# modEEGamp_v1_1.net
KiCad netlist of a schematic drawn in EAGLE
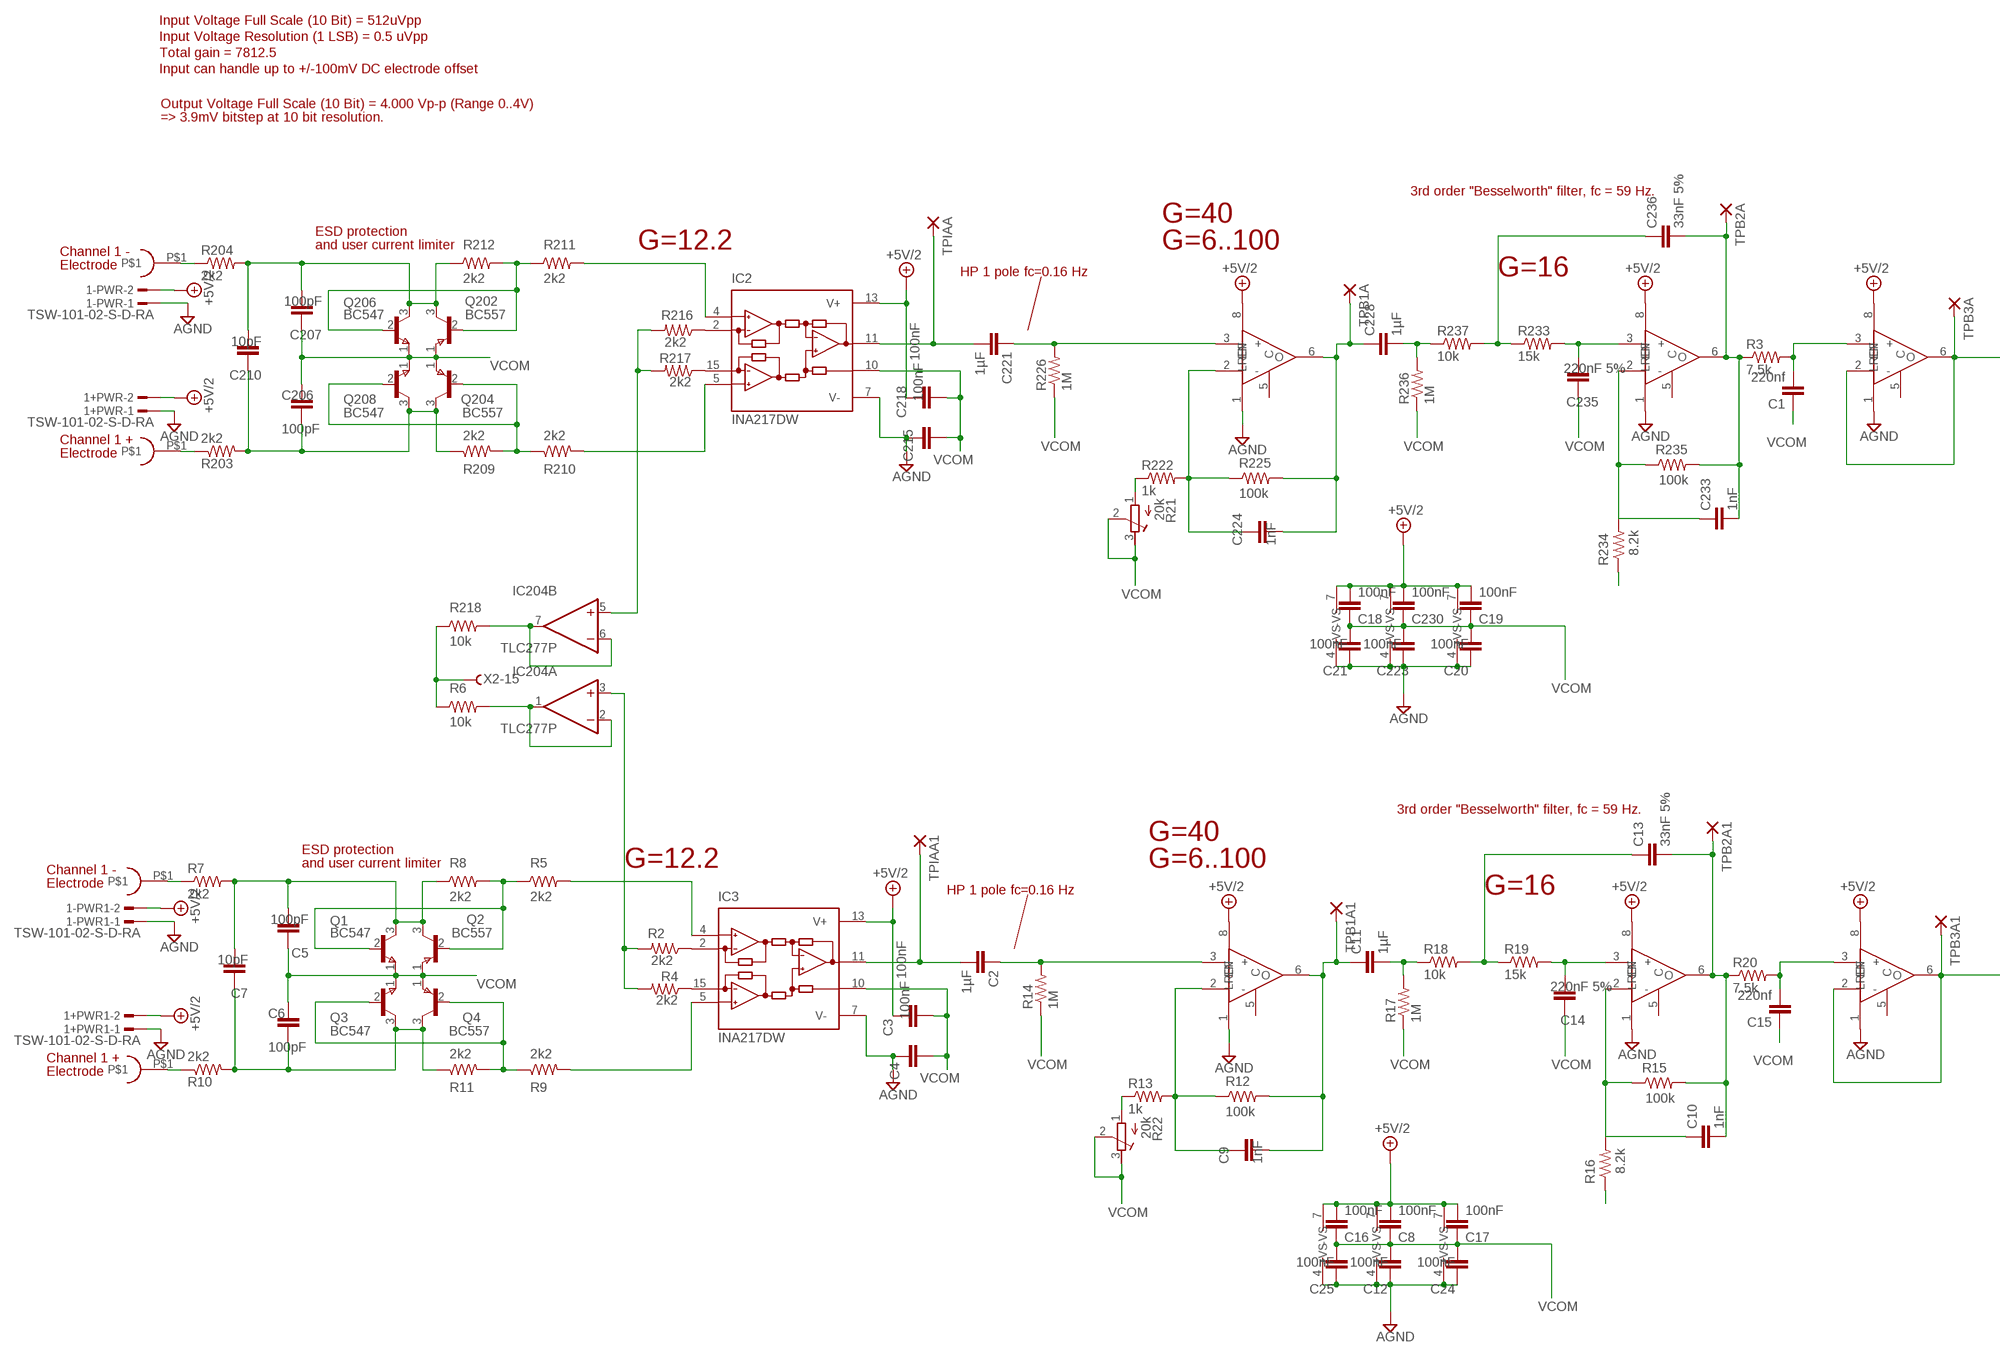
[diagram p0: schematic, sheet 1, part 1 of 2]
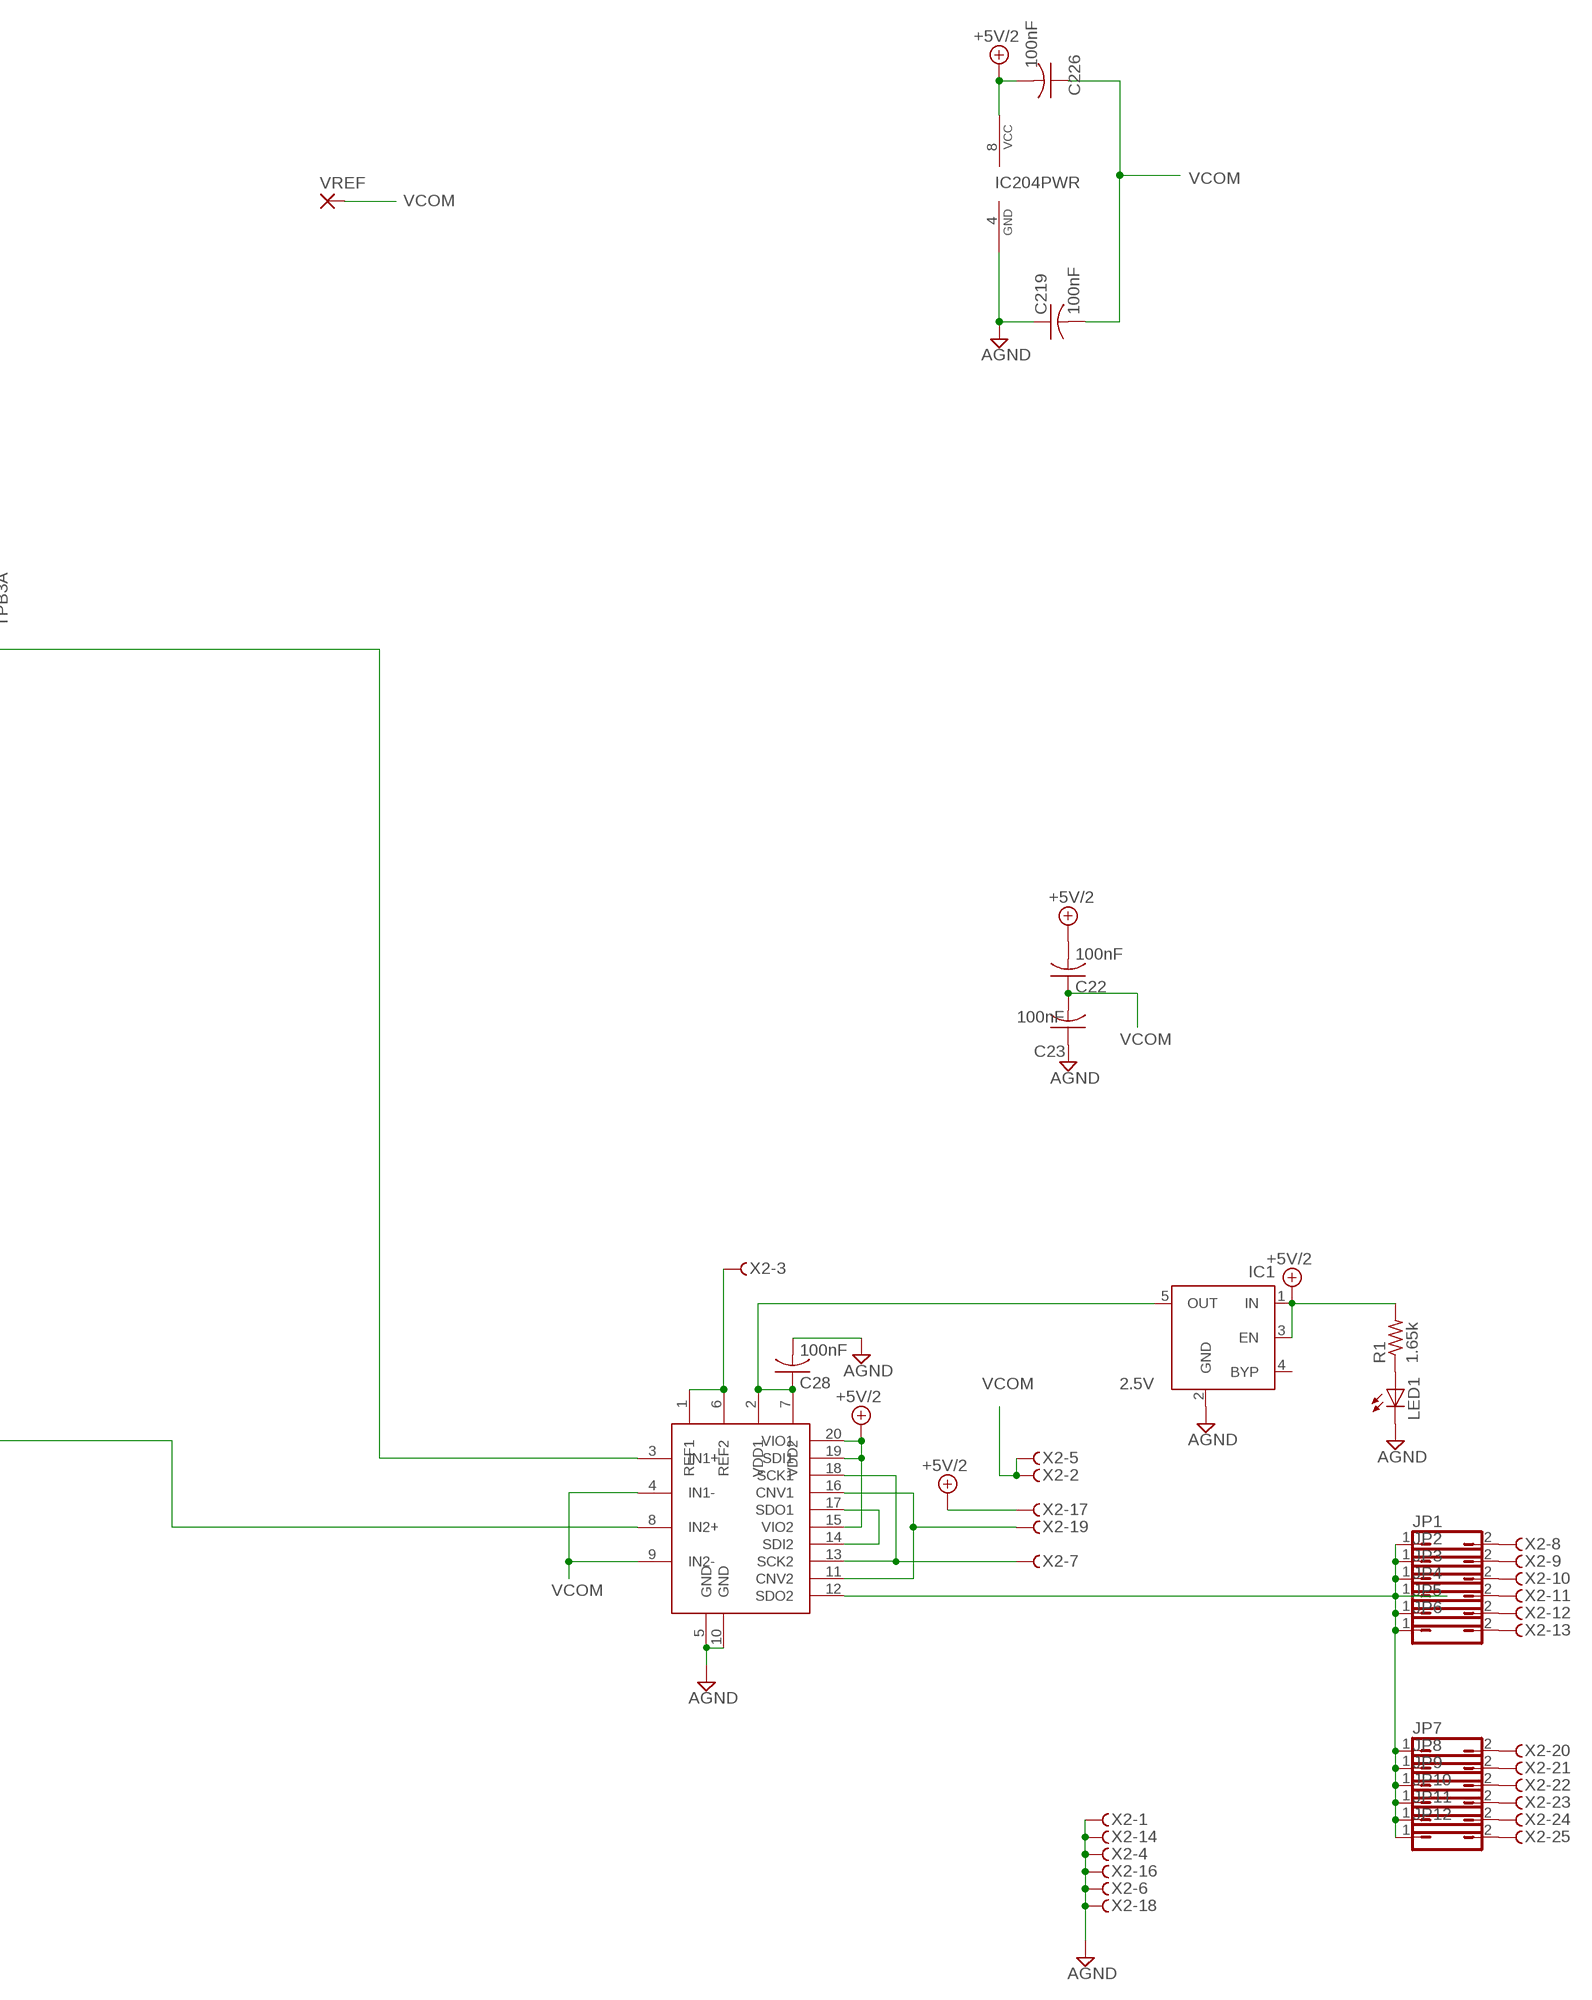
[diagram p1: schematic, sheet 1, part 2 of 2]

(export (version "E")
  (design (tool "Eeschema 10.0.6"))
  (components
    (comp (ref "1+PWR")
      (value "TSW-101-02-S-D-RA")
      (footprint "eagle-import:TSW-101-02-S-D-RA")
      (libsource (lib "eagle-import") (part "TSW-101-02-S-D-RA"))
    )
    (comp (ref "1+PWR1")
      (value "TSW-101-02-S-D-RA")
      (footprint "eagle-import:TSW-101-02-S-D-RA")
      (libsource (lib "eagle-import") (part "TSW-101-02-S-D-RA"))
    )
    (comp (ref "1-PWR")
      (value "TSW-101-02-S-D-RA")
      (footprint "eagle-import:TSW-101-02-S-D-RA")
      (libsource (lib "eagle-import") (part "TSW-101-02-S-D-RA"))
    )
    (comp (ref "1-PWR1")
      (value "TSW-101-02-S-D-RA")
      (footprint "eagle-import:TSW-101-02-S-D-RA")
      (libsource (lib "eagle-import") (part "TSW-101-02-S-D-RA"))
    )
    (comp (ref "C1")
      (value "220nf")
      (footprint "eagle-import:C1206")
      (libsource (lib "eagle-import") (part "C-EUC1206"))
    )
    (comp (ref "C1+")
      (value "DIN42802")
      (footprint "eagle-import:DIN42802")
      (libsource (lib "eagle-import") (part "DIN42802"))
    )
    (comp (ref "C1+1")
      (value "DIN42802")
      (footprint "eagle-import:DIN42802")
      (libsource (lib "eagle-import") (part "DIN42802"))
    )
    (comp (ref "C1-")
      (value "DIN42802")
      (footprint "eagle-import:DIN42802")
      (libsource (lib "eagle-import") (part "DIN42802"))
    )
    (comp (ref "C1-1")
      (value "DIN42802")
      (footprint "eagle-import:DIN42802")
      (libsource (lib "eagle-import") (part "DIN42802"))
    )
    (comp (ref "C2")
      (value "1µF")
      (footprint "eagle-import:C050-024X044")
      (libsource (lib "eagle-import") (part "C-EU050-024X044"))
    )
    (comp (ref "C3")
      (value "100nF")
      (footprint "eagle-import:C1206")
      (libsource (lib "eagle-import") (part "C-EUC1206"))
    )
    (comp (ref "C4")
      (value "100nF")
      (footprint "eagle-import:C1206")
      (libsource (lib "eagle-import") (part "C-EUC1206"))
    )
    (comp (ref "C5")
      (value "100pF")
      (footprint "eagle-import:C1206")
      (libsource (lib "eagle-import") (part "C-EUC1206"))
    )
    (comp (ref "C6")
      (value "100pF")
      (footprint "eagle-import:C1206")
      (libsource (lib "eagle-import") (part "C-EUC1206"))
    )
    (comp (ref "C7")
      (value "10pF")
      (footprint "eagle-import:C1206")
      (libsource (lib "eagle-import") (part "C-EUC1206"))
    )
    (comp (ref "C8")
      (value "100nF")
      (footprint "eagle-import:C1206")
      (libsource (lib "eagle-import") (part "C-EUC1206"))
    )
    (comp (ref "C9")
      (value "1nF")
      (footprint "eagle-import:C1206")
      (libsource (lib "eagle-import") (part "C-EUC1206"))
    )
    (comp (ref "C10")
      (value "1nF")
      (footprint "eagle-import:C1206")
      (libsource (lib "eagle-import") (part "C-EUC1206"))
    )
    (comp (ref "C11")
      (value "1µF")
      (footprint "eagle-import:C050-024X044")
      (libsource (lib "eagle-import") (part "C-EU050-024X044"))
    )
    (comp (ref "C12")
      (value "100nF")
      (footprint "eagle-import:C1206")
      (libsource (lib "eagle-import") (part "C-EUC1206"))
    )
    (comp (ref "C13")
      (value "33nF 5%")
      (footprint "eagle-import:C1206")
      (libsource (lib "eagle-import") (part "C-EUC1206"))
    )
    (comp (ref "C14")
      (value "220nF 5%")
      (footprint "eagle-import:C1206")
      (libsource (lib "eagle-import") (part "C-EUC1206"))
    )
    (comp (ref "C15")
      (value "220nf")
      (footprint "eagle-import:C1206")
      (libsource (lib "eagle-import") (part "C-EUC1206"))
    )
    (comp (ref "C16")
      (value "100nF")
      (footprint "eagle-import:C1206")
      (libsource (lib "eagle-import") (part "C-EUC1206"))
    )
    (comp (ref "C17")
      (value "100nF")
      (footprint "eagle-import:C1206")
      (libsource (lib "eagle-import") (part "C-EUC1206"))
    )
    (comp (ref "C18")
      (value "100nF")
      (footprint "eagle-import:C1206")
      (libsource (lib "eagle-import") (part "C-EUC1206"))
    )
    (comp (ref "C19")
      (value "100nF")
      (footprint "eagle-import:C1206")
      (libsource (lib "eagle-import") (part "C-EUC1206"))
    )
    (comp (ref "C20")
      (value "100nF")
      (footprint "eagle-import:C1206")
      (libsource (lib "eagle-import") (part "C-EUC1206"))
    )
    (comp (ref "C21")
      (value "100nF")
      (footprint "eagle-import:C1206")
      (libsource (lib "eagle-import") (part "C-EUC1206"))
    )
    (comp (ref "C22")
      (value "100nF")
      (footprint "eagle-import:C1206")
      (libsource (lib "eagle-import") (part "C-USC1206"))
    )
    (comp (ref "C23")
      (value "100nF")
      (footprint "eagle-import:C1206")
      (libsource (lib "eagle-import") (part "C-USC1206"))
    )
    (comp (ref "C24")
      (value "100nF")
      (footprint "eagle-import:C1206")
      (libsource (lib "eagle-import") (part "C-EUC1206"))
    )
    (comp (ref "C25")
      (value "100nF")
      (footprint "eagle-import:C1206")
      (libsource (lib "eagle-import") (part "C-EUC1206"))
    )
    (comp (ref "C28")
      (value "100nF")
      (footprint "eagle-import:C1206")
      (libsource (lib "eagle-import") (part "C-USC1206"))
    )
    (comp (ref "C206")
      (value "100pF")
      (footprint "eagle-import:C1206")
      (libsource (lib "eagle-import") (part "C-EUC1206"))
    )
    (comp (ref "C207")
      (value "100pF")
      (footprint "eagle-import:C1206")
      (libsource (lib "eagle-import") (part "C-EUC1206"))
    )
    (comp (ref "C210")
      (value "10pF")
      (footprint "eagle-import:C1206")
      (libsource (lib "eagle-import") (part "C-EUC1206"))
    )
    (comp (ref "C215")
      (value "100nF")
      (footprint "eagle-import:C1206")
      (libsource (lib "eagle-import") (part "C-EUC1206"))
    )
    (comp (ref "C218")
      (value "100nF")
      (footprint "eagle-import:C1206")
      (libsource (lib "eagle-import") (part "C-EUC1206"))
    )
    (comp (ref "C219")
      (value "100nF")
      (footprint "eagle-import:C1206")
      (libsource (lib "eagle-import") (part "C-USC1206"))
    )
    (comp (ref "C221")
      (value "1µF")
      (footprint "eagle-import:C050-024X044")
      (libsource (lib "eagle-import") (part "C-EU050-024X044"))
    )
    (comp (ref "C223")
      (value "100nF")
      (footprint "eagle-import:C1206")
      (libsource (lib "eagle-import") (part "C-EUC1206"))
    )
    (comp (ref "C224")
      (value "1nF")
      (footprint "eagle-import:C1206")
      (libsource (lib "eagle-import") (part "C-EUC1206"))
    )
    (comp (ref "C226")
      (value "100nF")
      (footprint "eagle-import:C1206")
      (libsource (lib "eagle-import") (part "C-USC1206"))
    )
    (comp (ref "C228")
      (value "1µF")
      (footprint "eagle-import:C050-024X044")
      (libsource (lib "eagle-import") (part "C-EU050-024X044"))
    )
    (comp (ref "C230")
      (value "100nF")
      (footprint "eagle-import:C1206")
      (libsource (lib "eagle-import") (part "C-EUC1206"))
    )
    (comp (ref "C233")
      (value "1nF")
      (footprint "eagle-import:C1206")
      (libsource (lib "eagle-import") (part "C-EUC1206"))
    )
    (comp (ref "C235")
      (value "220nF 5%")
      (footprint "eagle-import:C1206")
      (libsource (lib "eagle-import") (part "C-EUC1206"))
    )
    (comp (ref "C236")
      (value "33nF 5%")
      (footprint "eagle-import:C1206")
      (libsource (lib "eagle-import") (part "C-EUC1206"))
    )
    (comp (ref "IC1")
      (value "2.5V")
      (footprint "eagle-import:SOT23-5")
      (libsource (lib "eagle-import") (part "MIC5219XX"))
    )
    (comp (ref "IC2")
      (value "INA217DW")
      (footprint "eagle-import:DW_RPDSO-G16")
      (fields (field (name "MF") "TEXAS INSTRUMENTS") (field (name "MPN") "INA217AIDWT"))
      (libsource (lib "eagle-import") (part "INA217DW"))
    )
    (comp (ref "IC3")
      (value "INA217DW")
      (footprint "eagle-import:DW_RPDSO-G16")
      (fields (field (name "MF") "TEXAS INSTRUMENTS") (field (name "MPN") "INA217AIDWT"))
      (libsource (lib "eagle-import") (part "INA217DW"))
    )
    (comp (ref "IC204")
      (value "TLC277P")
      (footprint "eagle-import:DIL-08")
      (libsource (lib "eagle-import") (part "TLC277P"))
    )
    (comp (ref "JP1")
      (value "JP1Q")
      (footprint "eagle-import:JP1")
      (libsource (lib "eagle-import") (part "JP1Q"))
    )
    (comp (ref "JP2")
      (value "JP1Q")
      (footprint "eagle-import:JP1")
      (libsource (lib "eagle-import") (part "JP1Q"))
    )
    (comp (ref "JP3")
      (value "JP1Q")
      (footprint "eagle-import:JP1")
      (libsource (lib "eagle-import") (part "JP1Q"))
    )
    (comp (ref "JP4")
      (value "JP1Q")
      (footprint "eagle-import:JP1")
      (libsource (lib "eagle-import") (part "JP1Q"))
    )
    (comp (ref "JP5")
      (value "JP1Q")
      (footprint "eagle-import:JP1")
      (libsource (lib "eagle-import") (part "JP1Q"))
    )
    (comp (ref "JP6")
      (value "JP1Q")
      (footprint "eagle-import:JP1")
      (libsource (lib "eagle-import") (part "JP1Q"))
    )
    (comp (ref "JP7")
      (value "JP1Q")
      (footprint "eagle-import:JP1")
      (libsource (lib "eagle-import") (part "JP1Q"))
    )
    (comp (ref "JP8")
      (value "JP1Q")
      (footprint "eagle-import:JP1")
      (libsource (lib "eagle-import") (part "JP1Q"))
    )
    (comp (ref "JP9")
      (value "JP1Q")
      (footprint "eagle-import:JP1")
      (libsource (lib "eagle-import") (part "JP1Q"))
    )
    (comp (ref "JP10")
      (value "JP1Q")
      (footprint "eagle-import:JP1")
      (libsource (lib "eagle-import") (part "JP1Q"))
    )
    (comp (ref "JP11")
      (value "JP1Q")
      (footprint "eagle-import:JP1")
      (libsource (lib "eagle-import") (part "JP1Q"))
    )
    (comp (ref "JP12")
      (value "JP1Q")
      (footprint "eagle-import:JP1")
      (libsource (lib "eagle-import") (part "JP1Q"))
    )
    (comp (ref "LED1")
      (value "LED3MM")
      (footprint "eagle-import:LED3MM")
      (libsource (lib "eagle-import") (part "LED3MM"))
    )
    (comp (ref "Q1")
      (value "BC547")
      (footprint "eagle-import:TO92")
      (libsource (lib "eagle-import") (part "BC547"))
    )
    (comp (ref "Q2")
      (value "BC557")
      (footprint "eagle-import:TO92")
      (libsource (lib "eagle-import") (part "BC557"))
    )
    (comp (ref "Q3")
      (value "BC547")
      (footprint "eagle-import:TO92")
      (libsource (lib "eagle-import") (part "BC547"))
    )
    (comp (ref "Q4")
      (value "BC557")
      (footprint "eagle-import:TO92")
      (libsource (lib "eagle-import") (part "BC557"))
    )
    (comp (ref "Q202")
      (value "BC557")
      (footprint "eagle-import:TO92")
      (libsource (lib "eagle-import") (part "BC557"))
    )
    (comp (ref "Q204")
      (value "BC557")
      (footprint "eagle-import:TO92")
      (libsource (lib "eagle-import") (part "BC557"))
    )
    (comp (ref "Q206")
      (value "BC547")
      (footprint "eagle-import:TO92")
      (libsource (lib "eagle-import") (part "BC547"))
    )
    (comp (ref "Q208")
      (value "BC547")
      (footprint "eagle-import:TO92")
      (libsource (lib "eagle-import") (part "BC547"))
    )
    (comp (ref "R1")
      (value "1.65k")
      (footprint "eagle-import:R1206")
      (libsource (lib "eagle-import") (part "R-US_R1206"))
    )
    (comp (ref "R2")
      (value "2k2")
      (footprint "eagle-import:R1206")
      (libsource (lib "eagle-import") (part "R-US_R1206"))
    )
    (comp (ref "R3")
      (value "7.5k")
      (footprint "eagle-import:R1206")
      (libsource (lib "eagle-import") (part "R-US_R1206"))
    )
    (comp (ref "R4")
      (value "2k2")
      (footprint "eagle-import:R1206")
      (libsource (lib "eagle-import") (part "R-US_R1206"))
    )
    (comp (ref "R5")
      (value "2k2")
      (footprint "eagle-import:R1206")
      (libsource (lib "eagle-import") (part "R-US_R1206"))
    )
    (comp (ref "R6")
      (value "10k")
      (footprint "eagle-import:R1206")
      (libsource (lib "eagle-import") (part "R-US_R1206"))
    )
    (comp (ref "R7")
      (value "2k2")
      (footprint "eagle-import:R1206")
      (libsource (lib "eagle-import") (part "R-US_R1206"))
    )
    (comp (ref "R8")
      (value "2k2")
      (footprint "eagle-import:R1206")
      (libsource (lib "eagle-import") (part "R-US_R1206"))
    )
    (comp (ref "R9")
      (value "2k2")
      (footprint "eagle-import:R1206")
      (libsource (lib "eagle-import") (part "R-US_R1206"))
    )
    (comp (ref "R10")
      (value "2k2")
      (footprint "eagle-import:R1206")
      (libsource (lib "eagle-import") (part "R-US_R1206"))
    )
    (comp (ref "R11")
      (value "2k2")
      (footprint "eagle-import:R1206")
      (libsource (lib "eagle-import") (part "R-US_R1206"))
    )
    (comp (ref "R12")
      (value "100k")
      (footprint "eagle-import:R1206")
      (libsource (lib "eagle-import") (part "R-US_R1206"))
    )
    (comp (ref "R13")
      (value "1k")
      (footprint "eagle-import:R1206")
      (libsource (lib "eagle-import") (part "R-US_R1206"))
    )
    (comp (ref "R14")
      (value "1M")
      (footprint "eagle-import:R1206")
      (libsource (lib "eagle-import") (part "R-US_R1206"))
    )
    (comp (ref "R15")
      (value "100k")
      (footprint "eagle-import:R1206")
      (libsource (lib "eagle-import") (part "R-US_R1206"))
    )
    (comp (ref "R16")
      (value "8.2k")
      (footprint "eagle-import:R1206")
      (libsource (lib "eagle-import") (part "R-US_R1206"))
    )
    (comp (ref "R17")
      (value "1M")
      (footprint "eagle-import:R1206")
      (libsource (lib "eagle-import") (part "R-US_R1206"))
    )
    (comp (ref "R18")
      (value "10k")
      (footprint "eagle-import:R1206")
      (libsource (lib "eagle-import") (part "R-US_R1206"))
    )
    (comp (ref "R19")
      (value "15k")
      (footprint "eagle-import:R1206")
      (libsource (lib "eagle-import") (part "R-US_R1206"))
    )
    (comp (ref "R20")
      (value "7.5k")
      (footprint "eagle-import:R1206")
      (libsource (lib "eagle-import") (part "R-US_R1206"))
    )
    (comp (ref "R21")
      (value "20k")
      (footprint "eagle-import:RTRIM3296W")
      (libsource (lib "eagle-import") (part "R-TRIMM3296W"))
    )
    (comp (ref "R22")
      (value "20k")
      (footprint "eagle-import:RTRIM3296W")
      (libsource (lib "eagle-import") (part "R-TRIMM3296W"))
    )
    (comp (ref "R203")
      (value "2k2")
      (footprint "eagle-import:R1206")
      (libsource (lib "eagle-import") (part "R-US_R1206"))
    )
    (comp (ref "R204")
      (value "2k2")
      (footprint "eagle-import:R1206")
      (libsource (lib "eagle-import") (part "R-US_R1206"))
    )
    (comp (ref "R209")
      (value "2k2")
      (footprint "eagle-import:R1206")
      (libsource (lib "eagle-import") (part "R-US_R1206"))
    )
    (comp (ref "R210")
      (value "2k2")
      (footprint "eagle-import:R1206")
      (libsource (lib "eagle-import") (part "R-US_R1206"))
    )
    (comp (ref "R211")
      (value "2k2")
      (footprint "eagle-import:R1206")
      (libsource (lib "eagle-import") (part "R-US_R1206"))
    )
    (comp (ref "R212")
      (value "2k2")
      (footprint "eagle-import:R1206")
      (libsource (lib "eagle-import") (part "R-US_R1206"))
    )
    (comp (ref "R216")
      (value "2k2")
      (footprint "eagle-import:R1206")
      (libsource (lib "eagle-import") (part "R-US_R1206"))
    )
    (comp (ref "R217")
      (value "2k2")
      (footprint "eagle-import:R1206")
      (libsource (lib "eagle-import") (part "R-US_R1206"))
    )
    (comp (ref "R218")
      (value "10k")
      (footprint "eagle-import:R1206")
      (libsource (lib "eagle-import") (part "R-US_R1206"))
    )
    (comp (ref "R222")
      (value "1k")
      (footprint "eagle-import:R1206")
      (libsource (lib "eagle-import") (part "R-US_R1206"))
    )
    (comp (ref "R225")
      (value "100k")
      (footprint "eagle-import:R1206")
      (libsource (lib "eagle-import") (part "R-US_R1206"))
    )
    (comp (ref "R226")
      (value "1M")
      (footprint "eagle-import:R1206")
      (libsource (lib "eagle-import") (part "R-US_R1206"))
    )
    (comp (ref "R233")
      (value "15k")
      (footprint "eagle-import:R1206")
      (libsource (lib "eagle-import") (part "R-US_R1206"))
    )
    (comp (ref "R234")
      (value "8.2k")
      (footprint "eagle-import:R1206")
      (libsource (lib "eagle-import") (part "R-US_R1206"))
    )
    (comp (ref "R235")
      (value "100k")
      (footprint "eagle-import:R1206")
      (libsource (lib "eagle-import") (part "R-US_R1206"))
    )
    (comp (ref "R236")
      (value "1M")
      (footprint "eagle-import:R1206")
      (libsource (lib "eagle-import") (part "R-US_R1206"))
    )
    (comp (ref "R237")
      (value "10k")
      (footprint "eagle-import:R1206")
      (libsource (lib "eagle-import") (part "R-US_R1206"))
    )
    (comp (ref "TPB1A")
      (value "1,6/0,8")
      (footprint "eagle-import:1,6_0,8")
      (libsource (lib "eagle-import") (part "1,6/0,8"))
    )
    (comp (ref "TPB1A1")
      (value "1,6/0,8")
      (footprint "eagle-import:1,6_0,8")
      (libsource (lib "eagle-import") (part "1,6/0,8"))
    )
    (comp (ref "TPB2A")
      (value "1,6/0,8")
      (footprint "eagle-import:1,6_0,8")
      (libsource (lib "eagle-import") (part "1,6/0,8"))
    )
    (comp (ref "TPB2A1")
      (value "1,6/0,8")
      (footprint "eagle-import:1,6_0,8")
      (libsource (lib "eagle-import") (part "1,6/0,8"))
    )
    (comp (ref "TPB3A")
      (value "1,6/0,8")
      (footprint "eagle-import:1,6_0,8")
      (libsource (lib "eagle-import") (part "1,6/0,8"))
    )
    (comp (ref "TPB3A1")
      (value "1,6/0,8")
      (footprint "eagle-import:1,6_0,8")
      (libsource (lib "eagle-import") (part "1,6/0,8"))
    )
    (comp (ref "TPIAA")
      (value "1,6/0,8")
      (footprint "eagle-import:1,6_0,8")
      (libsource (lib "eagle-import") (part "1,6/0,8"))
    )
    (comp (ref "TPIAA1")
      (value "1,6/0,8")
      (footprint "eagle-import:1,6_0,8")
      (libsource (lib "eagle-import") (part "1,6/0,8"))
    )
    (comp (ref "U$1")
      (value "AD7902")
      (footprint "eagle-import:QSOP20")
      (libsource (lib "eagle-import") (part "AD7902"))
    )
    (comp (ref "U$10")
      (value "AD8021")
      (footprint "eagle-import:SOIC8")
      (libsource (lib "eagle-import") (part "AD8021"))
    )
    (comp (ref "U$12")
      (value "AD8021")
      (footprint "eagle-import:SOIC8")
      (libsource (lib "eagle-import") (part "AD8021"))
    )
    (comp (ref "U$20")
      (value "AD8021")
      (footprint "eagle-import:SOIC8")
      (libsource (lib "eagle-import") (part "AD8021"))
    )
    (comp (ref "U$30")
      (value "AD8021")
      (footprint "eagle-import:SOIC8")
      (libsource (lib "eagle-import") (part "AD8021"))
    )
    (comp (ref "U$31")
      (value "AD8021")
      (footprint "eagle-import:SOIC8")
      (libsource (lib "eagle-import") (part "AD8021"))
    )
    (comp (ref "U$36")
      (value "AD8021")
      (footprint "eagle-import:SOIC8")
      (libsource (lib "eagle-import") (part "AD8021"))
    )
    (comp (ref "VREF")
      (value "1,6/0,8")
      (footprint "eagle-import:1,6_0,8")
      (libsource (lib "eagle-import") (part "1,6/0,8"))
    )
    (comp (ref "X2")
      (value "F25HPS")
      (footprint "eagle-import:F25HP")
      (libsource (lib "eagle-import") (part "F25?SHP"))
    )
  )
  (nets
    (net (code "1") (name "+5V{slash}2") (class "Default")
      (node (ref "1+PWR") (pin "2") (pinfunction "1_2") (pintype "passive"))
      (node (ref "1+PWR1") (pin "2") (pinfunction "1_2") (pintype "passive"))
      (node (ref "1-PWR") (pin "2") (pinfunction "1_2") (pintype "passive"))
      (node (ref "1-PWR1") (pin "2") (pinfunction "1_2") (pintype "passive"))
      (node (ref "C16") (pin "2") (pinfunction "2_2") (pintype "passive"))
      (node (ref "C17") (pin "2") (pinfunction "2_2") (pintype "passive"))
      (node (ref "C18") (pin "2") (pinfunction "2_2") (pintype "passive"))
      (node (ref "C19") (pin "2") (pinfunction "2_2") (pintype "passive"))
      (node (ref "C218") (pin "1") (pinfunction "1_1") (pintype "passive"))
      (node (ref "C22") (pin "2") (pinfunction "2_2") (pintype "passive"))
      (node (ref "C226") (pin "2") (pinfunction "2_2") (pintype "passive"))
      (node (ref "C230") (pin "2") (pinfunction "2_2") (pintype "passive"))
      (node (ref "C3") (pin "1") (pinfunction "1_1") (pintype "passive"))
      (node (ref "C8") (pin "2") (pinfunction "2_2") (pintype "passive"))
      (node (ref "IC1") (pin "1") (pinfunction "IN_1") (pintype "input"))
      (node (ref "IC1") (pin "3") (pinfunction "EN_3") (pintype "input"))
      (node (ref "IC2") (pin "13") (pinfunction "V+_13") (pintype "power_in"))
      (node (ref "IC204") (pin "8") (pinfunction "VCC_8") (pintype "power_in"))
      (node (ref "IC3") (pin "13") (pinfunction "V+_13") (pintype "power_in"))
      (node (ref "R1") (pin "2") (pinfunction "2_2") (pintype "passive"))
      (node (ref "U$1") (pin "15") (pinfunction "VIO2_15") (pintype "bidirectional"))
      (node (ref "U$1") (pin "19") (pinfunction "SDI1_19") (pintype "bidirectional"))
      (node (ref "U$1") (pin "20") (pinfunction "VIO1_20") (pintype "bidirectional"))
      (node (ref "U$10") (pin "7") (pinfunction "+VS_7") (pintype "bidirectional"))
      (node (ref "U$10") (pin "8") (pinfunction "EN_8") (pintype "bidirectional"))
      (node (ref "U$12") (pin "7") (pinfunction "+VS_7") (pintype "bidirectional"))
      (node (ref "U$12") (pin "8") (pinfunction "EN_8") (pintype "bidirectional"))
      (node (ref "U$20") (pin "7") (pinfunction "+VS_7") (pintype "bidirectional"))
      (node (ref "U$20") (pin "8") (pinfunction "EN_8") (pintype "bidirectional"))
      (node (ref "U$30") (pin "7") (pinfunction "+VS_7") (pintype "bidirectional"))
      (node (ref "U$30") (pin "8") (pinfunction "EN_8") (pintype "bidirectional"))
      (node (ref "U$31") (pin "7") (pinfunction "+VS_7") (pintype "bidirectional"))
      (node (ref "U$31") (pin "8") (pinfunction "EN_8") (pintype "bidirectional"))
      (node (ref "U$36") (pin "7") (pinfunction "+VS_7") (pintype "bidirectional"))
      (node (ref "U$36") (pin "8") (pinfunction "EN_8") (pintype "bidirectional"))
      (node (ref "X2") (pin "17") (pinfunction "F_17") (pintype "passive"))
    )
    (net (code "2") (name "/VCOM") (class "Default")
      (node (ref "C1") (pin "1") (pinfunction "1_1") (pintype "passive"))
      (node (ref "C12") (pin "2") (pinfunction "2_2") (pintype "passive"))
      (node (ref "C14") (pin "1") (pinfunction "1_1") (pintype "passive"))
      (node (ref "C15") (pin "1") (pinfunction "1_1") (pintype "passive"))
      (node (ref "C16") (pin "1") (pinfunction "1_1") (pintype "passive"))
      (node (ref "C17") (pin "1") (pinfunction "1_1") (pintype "passive"))
      (node (ref "C18") (pin "1") (pinfunction "1_1") (pintype "passive"))
      (node (ref "C19") (pin "1") (pinfunction "1_1") (pintype "passive"))
      (node (ref "C20") (pin "2") (pinfunction "2_2") (pintype "passive"))
      (node (ref "C206") (pin "2") (pinfunction "2_2") (pintype "passive"))
      (node (ref "C207") (pin "1") (pinfunction "1_1") (pintype "passive"))
      (node (ref "C21") (pin "2") (pinfunction "2_2") (pintype "passive"))
      (node (ref "C215") (pin "2") (pinfunction "2_2") (pintype "passive"))
      (node (ref "C218") (pin "2") (pinfunction "2_2") (pintype "passive"))
      (node (ref "C219") (pin "2") (pinfunction "2_2") (pintype "passive"))
      (node (ref "C22") (pin "1") (pinfunction "1_1") (pintype "passive"))
      (node (ref "C223") (pin "2") (pinfunction "2_2") (pintype "passive"))
      (node (ref "C226") (pin "1") (pinfunction "1_1") (pintype "passive"))
      (node (ref "C23") (pin "2") (pinfunction "2_2") (pintype "passive"))
      (node (ref "C230") (pin "1") (pinfunction "1_1") (pintype "passive"))
      (node (ref "C235") (pin "1") (pinfunction "1_1") (pintype "passive"))
      (node (ref "C24") (pin "2") (pinfunction "2_2") (pintype "passive"))
      (node (ref "C25") (pin "2") (pinfunction "2_2") (pintype "passive"))
      (node (ref "C3") (pin "2") (pinfunction "2_2") (pintype "passive"))
      (node (ref "C4") (pin "2") (pinfunction "2_2") (pintype "passive"))
      (node (ref "C5") (pin "1") (pinfunction "1_1") (pintype "passive"))
      (node (ref "C6") (pin "2") (pinfunction "2_2") (pintype "passive"))
      (node (ref "C8") (pin "1") (pinfunction "1_1") (pintype "passive"))
      (node (ref "IC2") (pin "10") (pinfunction "REF_10") (pintype "passive"))
      (node (ref "IC3") (pin "10") (pinfunction "REF_10") (pintype "passive"))
      (node (ref "Q1") (pin "1") (pinfunction "E_1") (pintype "passive"))
      (node (ref "Q2") (pin "1") (pinfunction "E_1") (pintype "passive"))
      (node (ref "Q202") (pin "1") (pinfunction "E_1") (pintype "passive"))
      (node (ref "Q204") (pin "1") (pinfunction "E_1") (pintype "passive"))
      (node (ref "Q206") (pin "1") (pinfunction "E_1") (pintype "passive"))
      (node (ref "Q208") (pin "1") (pinfunction "E_1") (pintype "passive"))
      (node (ref "Q3") (pin "1") (pinfunction "E_1") (pintype "passive"))
      (node (ref "Q4") (pin "1") (pinfunction "E_1") (pintype "passive"))
      (node (ref "R14") (pin "1") (pinfunction "1_1") (pintype "passive"))
      (node (ref "R16") (pin "1") (pinfunction "1_1") (pintype "passive"))
      (node (ref "R17") (pin "1") (pinfunction "1_1") (pintype "passive"))
      (node (ref "R21") (pin "2") (pinfunction "S_2") (pintype "passive"))
      (node (ref "R21") (pin "3") (pinfunction "E_3") (pintype "passive"))
      (node (ref "R22") (pin "2") (pinfunction "S_2") (pintype "passive"))
      (node (ref "R22") (pin "3") (pinfunction "E_3") (pintype "passive"))
      (node (ref "R226") (pin "1") (pinfunction "1_1") (pintype "passive"))
      (node (ref "R234") (pin "1") (pinfunction "1_1") (pintype "passive"))
      (node (ref "R236") (pin "1") (pinfunction "1_1") (pintype "passive"))
      (node (ref "U$1") (pin "4") (pinfunction "IN1-_4") (pintype "bidirectional"))
      (node (ref "U$1") (pin "9") (pinfunction "IN2-_9") (pintype "bidirectional"))
      (node (ref "VREF") (pin "1") (pinfunction "P_1") (pintype "passive"))
      (node (ref "X2") (pin "2") (pinfunction "F_2") (pintype "passive"))
      (node (ref "X2") (pin "5") (pinfunction "F_5") (pintype "passive"))
    )
    (net (code "3") (name "AGND") (class "Default")
      (node (ref "1+PWR") (pin "1") (pinfunction "1_1") (pintype "passive"))
      (node (ref "1+PWR1") (pin "1") (pinfunction "1_1") (pintype "passive"))
      (node (ref "1-PWR") (pin "1") (pinfunction "1_1") (pintype "passive"))
      (node (ref "1-PWR1") (pin "1") (pinfunction "1_1") (pintype "passive"))
      (node (ref "C12") (pin "1") (pinfunction "1_1") (pintype "passive"))
      (node (ref "C20") (pin "1") (pinfunction "1_1") (pintype "passive"))
      (node (ref "C21") (pin "1") (pinfunction "1_1") (pintype "passive"))
      (node (ref "C215") (pin "1") (pinfunction "1_1") (pintype "passive"))
      (node (ref "C219") (pin "1") (pinfunction "1_1") (pintype "passive"))
      (node (ref "C223") (pin "1") (pinfunction "1_1") (pintype "passive"))
      (node (ref "C23") (pin "1") (pinfunction "1_1") (pintype "passive"))
      (node (ref "C24") (pin "1") (pinfunction "1_1") (pintype "passive"))
      (node (ref "C25") (pin "1") (pinfunction "1_1") (pintype "passive"))
      (node (ref "C28") (pin "2") (pinfunction "2_2") (pintype "passive"))
      (node (ref "C4") (pin "1") (pinfunction "1_1") (pintype "passive"))
      (node (ref "IC1") (pin "2") (pinfunction "GND_2") (pintype "power_in"))
      (node (ref "IC2") (pin "7") (pinfunction "V-_7") (pintype "power_in"))
      (node (ref "IC204") (pin "4") (pinfunction "GND_4") (pintype "power_in"))
      (node (ref "IC3") (pin "7") (pinfunction "V-_7") (pintype "power_in"))
      (node (ref "LED1") (pin "K") (pinfunction "C_K") (pintype "passive"))
      (node (ref "U$1") (pin "10") (pinfunction "GND_10") (pintype "bidirectional"))
      (node (ref "U$1") (pin "5") (pinfunction "GND_5") (pintype "bidirectional"))
      (node (ref "U$10") (pin "1") (pinfunction "LREF_1") (pintype "bidirectional"))
      (node (ref "U$10") (pin "4") (pinfunction "-VS_4") (pintype "bidirectional"))
      (node (ref "U$12") (pin "1") (pinfunction "LREF_1") (pintype "bidirectional"))
      (node (ref "U$12") (pin "4") (pinfunction "-VS_4") (pintype "bidirectional"))
      (node (ref "U$20") (pin "1") (pinfunction "LREF_1") (pintype "bidirectional"))
      (node (ref "U$20") (pin "4") (pinfunction "-VS_4") (pintype "bidirectional"))
      (node (ref "U$30") (pin "1") (pinfunction "LREF_1") (pintype "bidirectional"))
      (node (ref "U$30") (pin "4") (pinfunction "-VS_4") (pintype "bidirectional"))
      (node (ref "U$31") (pin "1") (pinfunction "LREF_1") (pintype "bidirectional"))
      (node (ref "U$31") (pin "4") (pinfunction "-VS_4") (pintype "bidirectional"))
      (node (ref "U$36") (pin "1") (pinfunction "LREF_1") (pintype "bidirectional"))
      (node (ref "U$36") (pin "4") (pinfunction "-VS_4") (pintype "bidirectional"))
      (node (ref "X2") (pin "1") (pinfunction "F_1") (pintype "passive"))
      (node (ref "X2") (pin "14") (pinfunction "F_14") (pintype "passive"))
      (node (ref "X2") (pin "16") (pinfunction "F_16") (pintype "passive"))
      (node (ref "X2") (pin "18") (pinfunction "F_18") (pintype "passive"))
      (node (ref "X2") (pin "4") (pinfunction "F_4") (pintype "passive"))
      (node (ref "X2") (pin "6") (pinfunction "F_6") (pintype "passive"))
    )
    (net (code "4") (name "Net-(C1+-PadP$1)") (class "Default")
      (node (ref "C1+") (pin "P$1") (pinfunction "P$1_P$1") (pintype "bidirectional"))
      (node (ref "R203") (pin "1") (pinfunction "1_1") (pintype "passive"))
    )
    (net (code "5") (name "Net-(C1+1-PadP$1)") (class "Default")
      (node (ref "C1+1") (pin "P$1") (pinfunction "P$1_P$1") (pintype "bidirectional"))
      (node (ref "R10") (pin "1") (pinfunction "1_1") (pintype "passive"))
    )
    (net (code "6") (name "Net-(C1--PadP$1)") (class "Default")
      (node (ref "C1-") (pin "P$1") (pinfunction "P$1_P$1") (pintype "bidirectional"))
      (node (ref "R204") (pin "1") (pinfunction "1_1") (pintype "passive"))
    )
    (net (code "7") (name "Net-(C1-1-PadP$1)") (class "Default")
      (node (ref "C1-1") (pin "P$1") (pinfunction "P$1_P$1") (pintype "bidirectional"))
      (node (ref "R7") (pin "1") (pinfunction "1_1") (pintype "passive"))
    )
    (net (code "8") (name "Net-(C11-Pad2)") (class "Default")
      (node (ref "C11") (pin "2") (pinfunction "2_2") (pintype "passive"))
      (node (ref "R17") (pin "2") (pinfunction "2_2") (pintype "passive"))
      (node (ref "R18") (pin "1") (pinfunction "1_1") (pintype "passive"))
    )
    (net (code "9") (name "Net-(C13-Pad1)") (class "Default")
      (node (ref "C13") (pin "1") (pinfunction "1_1") (pintype "passive"))
      (node (ref "R18") (pin "2") (pinfunction "2_2") (pintype "passive"))
      (node (ref "R19") (pin "1") (pinfunction "1_1") (pintype "passive"))
    )
    (net (code "10") (name "Net-(C228-Pad2)") (class "Default")
      (node (ref "C228") (pin "2") (pinfunction "2_2") (pintype "passive"))
      (node (ref "R236") (pin "2") (pinfunction "2_2") (pintype "passive"))
      (node (ref "R237") (pin "1") (pinfunction "1_1") (pintype "passive"))
    )
    (net (code "11") (name "Net-(C236-Pad1)") (class "Default")
      (node (ref "C236") (pin "1") (pinfunction "1_1") (pintype "passive"))
      (node (ref "R233") (pin "1") (pinfunction "1_1") (pintype "passive"))
      (node (ref "R237") (pin "2") (pinfunction "2_2") (pintype "passive"))
    )
    (net (code "12") (name "Net-(IC1-OUT)") (class "Default")
      (node (ref "C28") (pin "1") (pinfunction "1_1") (pintype "passive"))
      (node (ref "IC1") (pin "5") (pinfunction "OUT_5") (pintype "output"))
      (node (ref "U$1") (pin "2") (pinfunction "VDD1_2") (pintype "bidirectional"))
      (node (ref "U$1") (pin "7") (pinfunction "VDD2_7") (pintype "bidirectional"))
    )
    (net (code "13") (name "Net-(IC2-+IN)") (class "Default")
      (node (ref "IC2") (pin "5") (pinfunction "+IN_5") (pintype "input"))
      (node (ref "R210") (pin "2") (pinfunction "2_2") (pintype "passive"))
    )
    (net (code "14") (name "Net-(IC2--IN)") (class "Default")
      (node (ref "IC2") (pin "4") (pinfunction "-IN_4") (pintype "input"))
      (node (ref "R211") (pin "2") (pinfunction "2_2") (pintype "passive"))
    )
    (net (code "15") (name "Net-(IC2-OUT)") (class "Default")
      (node (ref "C221") (pin "2") (pinfunction "2_2") (pintype "passive"))
      (node (ref "IC2") (pin "11") (pinfunction "OUT_11") (pintype "output"))
      (node (ref "TPIAA") (pin "1") (pinfunction "P_1") (pintype "passive"))
    )
    (net (code "16") (name "Net-(IC2-RG1)") (class "Default")
      (node (ref "IC2") (pin "2") (pinfunction "RG1_2") (pintype "passive"))
      (node (ref "R216") (pin "1") (pinfunction "1_1") (pintype "passive"))
    )
    (net (code "17") (name "Net-(IC2-RG2)") (class "Default")
      (node (ref "IC2") (pin "15") (pinfunction "RG2_15") (pintype "passive"))
      (node (ref "R217") (pin "1") (pinfunction "1_1") (pintype "passive"))
    )
    (net (code "18") (name "Net-(IC3-+IN)") (class "Default")
      (node (ref "IC3") (pin "5") (pinfunction "+IN_5") (pintype "input"))
      (node (ref "R9") (pin "2") (pinfunction "2_2") (pintype "passive"))
    )
    (net (code "19") (name "Net-(IC3--IN)") (class "Default")
      (node (ref "IC3") (pin "4") (pinfunction "-IN_4") (pintype "input"))
      (node (ref "R5") (pin "2") (pinfunction "2_2") (pintype "passive"))
    )
    (net (code "20") (name "Net-(IC3-OUT)") (class "Default")
      (node (ref "C2") (pin "2") (pinfunction "2_2") (pintype "passive"))
      (node (ref "IC3") (pin "11") (pinfunction "OUT_11") (pintype "output"))
      (node (ref "TPIAA1") (pin "1") (pinfunction "P_1") (pintype "passive"))
    )
    (net (code "21") (name "Net-(IC3-RG1)") (class "Default")
      (node (ref "IC3") (pin "2") (pinfunction "RG1_2") (pintype "passive"))
      (node (ref "R2") (pin "1") (pinfunction "1_1") (pintype "passive"))
    )
    (net (code "22") (name "Net-(IC3-RG2)") (class "Default")
      (node (ref "IC3") (pin "15") (pinfunction "RG2_15") (pintype "passive"))
      (node (ref "R4") (pin "1") (pinfunction "1_1") (pintype "passive"))
    )
    (net (code "23") (name "Net-(IC204A-+IN)") (class "Default")
      (node (ref "IC204") (pin "3") (pinfunction "+IN_3") (pintype "input"))
      (node (ref "R2") (pin "2") (pinfunction "2_2") (pintype "passive"))
      (node (ref "R4") (pin "2") (pinfunction "2_2") (pintype "passive"))
    )
    (net (code "24") (name "Net-(IC204A--IN)") (class "Default")
      (node (ref "IC204") (pin "1") (pinfunction "OUT_1") (pintype "output"))
      (node (ref "IC204") (pin "2") (pinfunction "-IN_2") (pintype "input"))
      (node (ref "R6") (pin "2") (pinfunction "2_2") (pintype "passive"))
    )
    (net (code "25") (name "Net-(IC204B-+IN)") (class "Default")
      (node (ref "IC204") (pin "5") (pinfunction "+IN_5") (pintype "input"))
      (node (ref "R216") (pin "2") (pinfunction "2_2") (pintype "passive"))
      (node (ref "R217") (pin "2") (pinfunction "2_2") (pintype "passive"))
    )
    (net (code "26") (name "Net-(IC204B--IN)") (class "Default")
      (node (ref "IC204") (pin "6") (pinfunction "-IN_6") (pintype "input"))
      (node (ref "IC204") (pin "7") (pinfunction "OUT_7") (pintype "output"))
      (node (ref "R218") (pin "2") (pinfunction "2_2") (pintype "passive"))
    )
    (net (code "27") (name "Net-(LED1-PadA)") (class "Default")
      (node (ref "LED1") (pin "A") (pinfunction "A_A") (pintype "passive"))
      (node (ref "R1") (pin "1") (pinfunction "1_1") (pintype "passive"))
    )
    (net (code "28") (name "Net-(Q1-B)") (class "Default")
      (node (ref "Q1") (pin "2") (pinfunction "B_2") (pintype "passive"))
      (node (ref "Q2") (pin "2") (pinfunction "B_2") (pintype "passive"))
      (node (ref "R5") (pin "1") (pinfunction "1_1") (pintype "passive"))
      (node (ref "R8") (pin "2") (pinfunction "2_2") (pintype "passive"))
    )
    (net (code "29") (name "Net-(Q1-C)") (class "Default")
      (node (ref "C5") (pin "2") (pinfunction "2_2") (pintype "passive"))
      (node (ref "C7") (pin "2") (pinfunction "2_2") (pintype "passive"))
      (node (ref "Q1") (pin "3") (pinfunction "C_3") (pintype "passive"))
      (node (ref "Q2") (pin "3") (pinfunction "C_3") (pintype "passive"))
      (node (ref "R7") (pin "2") (pinfunction "2_2") (pintype "passive"))
      (node (ref "R8") (pin "1") (pinfunction "1_1") (pintype "passive"))
    )
    (net (code "30") (name "Net-(Q3-B)") (class "Default")
      (node (ref "Q3") (pin "2") (pinfunction "B_2") (pintype "passive"))
      (node (ref "Q4") (pin "2") (pinfunction "B_2") (pintype "passive"))
      (node (ref "R11") (pin "2") (pinfunction "2_2") (pintype "passive"))
      (node (ref "R9") (pin "1") (pinfunction "1_1") (pintype "passive"))
    )
    (net (code "31") (name "Net-(Q3-C)") (class "Default")
      (node (ref "C6") (pin "1") (pinfunction "1_1") (pintype "passive"))
      (node (ref "C7") (pin "1") (pinfunction "1_1") (pintype "passive"))
      (node (ref "Q3") (pin "3") (pinfunction "C_3") (pintype "passive"))
      (node (ref "Q4") (pin "3") (pinfunction "C_3") (pintype "passive"))
      (node (ref "R10") (pin "2") (pinfunction "2_2") (pintype "passive"))
      (node (ref "R11") (pin "1") (pinfunction "1_1") (pintype "passive"))
    )
    (net (code "32") (name "Net-(Q202-B)") (class "Default")
      (node (ref "Q202") (pin "2") (pinfunction "B_2") (pintype "passive"))
      (node (ref "Q206") (pin "2") (pinfunction "B_2") (pintype "passive"))
      (node (ref "R211") (pin "1") (pinfunction "1_1") (pintype "passive"))
      (node (ref "R212") (pin "2") (pinfunction "2_2") (pintype "passive"))
    )
    (net (code "33") (name "Net-(Q202-C)") (class "Default")
      (node (ref "C207") (pin "2") (pinfunction "2_2") (pintype "passive"))
      (node (ref "C210") (pin "2") (pinfunction "2_2") (pintype "passive"))
      (node (ref "Q202") (pin "3") (pinfunction "C_3") (pintype "passive"))
      (node (ref "Q206") (pin "3") (pinfunction "C_3") (pintype "passive"))
      (node (ref "R204") (pin "2") (pinfunction "2_2") (pintype "passive"))
      (node (ref "R212") (pin "1") (pinfunction "1_1") (pintype "passive"))
    )
    (net (code "34") (name "Net-(Q204-B)") (class "Default")
      (node (ref "Q204") (pin "2") (pinfunction "B_2") (pintype "passive"))
      (node (ref "Q208") (pin "2") (pinfunction "B_2") (pintype "passive"))
      (node (ref "R209") (pin "2") (pinfunction "2_2") (pintype "passive"))
      (node (ref "R210") (pin "1") (pinfunction "1_1") (pintype "passive"))
    )
    (net (code "35") (name "Net-(Q204-C)") (class "Default")
      (node (ref "C206") (pin "1") (pinfunction "1_1") (pintype "passive"))
      (node (ref "C210") (pin "1") (pinfunction "1_1") (pintype "passive"))
      (node (ref "Q204") (pin "3") (pinfunction "C_3") (pintype "passive"))
      (node (ref "Q208") (pin "3") (pinfunction "C_3") (pintype "passive"))
      (node (ref "R203") (pin "2") (pinfunction "2_2") (pintype "passive"))
      (node (ref "R209") (pin "1") (pinfunction "1_1") (pintype "passive"))
    )
    (net (code "36") (name "Net-(R21-A)") (class "Default")
      (node (ref "R21") (pin "1") (pinfunction "A_1") (pintype "passive"))
      (node (ref "R222") (pin "1") (pinfunction "1_1") (pintype "passive"))
    )
    (net (code "37") (name "Net-(R22-A)") (class "Default")
      (node (ref "R13") (pin "1") (pinfunction "1_1") (pintype "passive"))
      (node (ref "R22") (pin "1") (pinfunction "A_1") (pintype "passive"))
    )
    (net (code "38") (name "Net-(TPB1A-P)") (class "Default")
      (node (ref "C224") (pin "2") (pinfunction "2_2") (pintype "passive"))
      (node (ref "C228") (pin "1") (pinfunction "1_1") (pintype "passive"))
      (node (ref "R225") (pin "2") (pinfunction "2_2") (pintype "passive"))
      (node (ref "TPB1A") (pin "1") (pinfunction "P_1") (pintype "passive"))
      (node (ref "U$10") (pin "6") (pinfunction "O_6") (pintype "bidirectional"))
    )
    (net (code "39") (name "Net-(TPB1A1-P)") (class "Default")
      (node (ref "C11") (pin "1") (pinfunction "1_1") (pintype "passive"))
      (node (ref "C9") (pin "2") (pinfunction "2_2") (pintype "passive"))
      (node (ref "R12") (pin "2") (pinfunction "2_2") (pintype "passive"))
      (node (ref "TPB1A1") (pin "1") (pinfunction "P_1") (pintype "passive"))
      (node (ref "U$30") (pin "6") (pinfunction "O_6") (pintype "bidirectional"))
    )
    (net (code "40") (name "Net-(TPB2A-P)") (class "Default")
      (node (ref "C233") (pin "2") (pinfunction "2_2") (pintype "passive"))
      (node (ref "C236") (pin "2") (pinfunction "2_2") (pintype "passive"))
      (node (ref "R235") (pin "2") (pinfunction "2_2") (pintype "passive"))
      (node (ref "R3") (pin "1") (pinfunction "1_1") (pintype "passive"))
      (node (ref "TPB2A") (pin "1") (pinfunction "P_1") (pintype "passive"))
      (node (ref "U$12") (pin "6") (pinfunction "O_6") (pintype "bidirectional"))
    )
    (net (code "41") (name "Net-(TPB2A1-P)") (class "Default")
      (node (ref "C10") (pin "2") (pinfunction "2_2") (pintype "passive"))
      (node (ref "C13") (pin "2") (pinfunction "2_2") (pintype "passive"))
      (node (ref "R15") (pin "2") (pinfunction "2_2") (pintype "passive"))
      (node (ref "R20") (pin "1") (pinfunction "1_1") (pintype "passive"))
      (node (ref "TPB2A1") (pin "1") (pinfunction "P_1") (pintype "passive"))
      (node (ref "U$31") (pin "6") (pinfunction "O_6") (pintype "bidirectional"))
    )
    (net (code "42") (name "Net-(TPB3A-P)") (class "Default")
      (node (ref "TPB3A") (pin "1") (pinfunction "P_1") (pintype "passive"))
      (node (ref "U$1") (pin "3") (pinfunction "IN1+_3") (pintype "bidirectional"))
      (node (ref "U$20") (pin "2") (pinfunction "-_2") (pintype "bidirectional"))
      (node (ref "U$20") (pin "6") (pinfunction "O_6") (pintype "bidirectional"))
    )
    (net (code "43") (name "Net-(TPB3A1-P)") (class "Default")
      (node (ref "TPB3A1") (pin "1") (pinfunction "P_1") (pintype "passive"))
      (node (ref "U$1") (pin "8") (pinfunction "IN2+_8") (pintype "bidirectional"))
      (node (ref "U$36") (pin "2") (pinfunction "-_2") (pintype "bidirectional"))
      (node (ref "U$36") (pin "6") (pinfunction "O_6") (pintype "bidirectional"))
    )
    (net (code "44") (name "Net-(U$1-CNV1)") (class "Default")
      (node (ref "U$1") (pin "11") (pinfunction "CNV2_11") (pintype "bidirectional"))
      (node (ref "U$1") (pin "16") (pinfunction "CNV1_16") (pintype "bidirectional"))
      (node (ref "X2") (pin "19") (pinfunction "F_19") (pintype "passive"))
    )
    (net (code "45") (name "Net-(U$1-REF1)") (class "Default")
      (node (ref "U$1") (pin "1") (pinfunction "REF1_1") (pintype "bidirectional"))
      (node (ref "U$1") (pin "6") (pinfunction "REF2_6") (pintype "bidirectional"))
      (node (ref "X2") (pin "3") (pinfunction "F_3") (pintype "passive"))
    )
    (net (code "46") (name "Net-(U$1-SCK1)") (class "Default")
      (node (ref "U$1") (pin "13") (pinfunction "SCK2_13") (pintype "bidirectional"))
      (node (ref "U$1") (pin "18") (pinfunction "SCK1_18") (pintype "bidirectional"))
      (node (ref "X2") (pin "7") (pinfunction "F_7") (pintype "passive"))
    )
    (net (code "47") (name "Net-(U$1-SDI2)") (class "Default")
      (node (ref "U$1") (pin "14") (pinfunction "SDI2_14") (pintype "bidirectional"))
      (node (ref "U$1") (pin "17") (pinfunction "SDO1_17") (pintype "bidirectional"))
    )
    (net (code "48") (name "Net-(U$1-SDO2)") (class "Default")
      (node (ref "JP1") (pin "1") (pinfunction "1_1") (pintype "passive"))
      (node (ref "JP10") (pin "1") (pinfunction "1_1") (pintype "passive"))
      (node (ref "JP11") (pin "1") (pinfunction "1_1") (pintype "passive"))
      (node (ref "JP12") (pin "1") (pinfunction "1_1") (pintype "passive"))
      (node (ref "JP2") (pin "1") (pinfunction "1_1") (pintype "passive"))
      (node (ref "JP3") (pin "1") (pinfunction "1_1") (pintype "passive"))
      (node (ref "JP4") (pin "1") (pinfunction "1_1") (pintype "passive"))
      (node (ref "JP5") (pin "1") (pinfunction "1_1") (pintype "passive"))
      (node (ref "JP6") (pin "1") (pinfunction "1_1") (pintype "passive"))
      (node (ref "JP7") (pin "1") (pinfunction "1_1") (pintype "passive"))
      (node (ref "JP8") (pin "1") (pinfunction "1_1") (pintype "passive"))
      (node (ref "JP9") (pin "1") (pinfunction "1_1") (pintype "passive"))
      (node (ref "U$1") (pin "12") (pinfunction "SDO2_12") (pintype "bidirectional"))
    )
    (net (code "49") (name "Net-(U$10A-+)") (class "Default")
      (node (ref "C221") (pin "1") (pinfunction "1_1") (pintype "passive"))
      (node (ref "R226") (pin "2") (pinfunction "2_2") (pintype "passive"))
      (node (ref "U$10") (pin "3") (pinfunction "+_3") (pintype "bidirectional"))
    )
    (net (code "50") (name "Net-(U$10A--)") (class "Default")
      (node (ref "C224") (pin "1") (pinfunction "1_1") (pintype "passive"))
      (node (ref "R222") (pin "2") (pinfunction "2_2") (pintype "passive"))
      (node (ref "R225") (pin "1") (pinfunction "1_1") (pintype "passive"))
      (node (ref "U$10") (pin "2") (pinfunction "-_2") (pintype "bidirectional"))
    )
    (net (code "51") (name "Net-(U$12A-+)") (class "Default")
      (node (ref "C235") (pin "2") (pinfunction "2_2") (pintype "passive"))
      (node (ref "R233") (pin "2") (pinfunction "2_2") (pintype "passive"))
      (node (ref "U$12") (pin "3") (pinfunction "+_3") (pintype "bidirectional"))
    )
    (net (code "52") (name "Net-(U$12A--)") (class "Default")
      (node (ref "C233") (pin "1") (pinfunction "1_1") (pintype "passive"))
      (node (ref "R234") (pin "2") (pinfunction "2_2") (pintype "passive"))
      (node (ref "R235") (pin "1") (pinfunction "1_1") (pintype "passive"))
      (node (ref "U$12") (pin "2") (pinfunction "-_2") (pintype "bidirectional"))
    )
    (net (code "53") (name "Net-(U$20A-+)") (class "Default")
      (node (ref "C1") (pin "2") (pinfunction "2_2") (pintype "passive"))
      (node (ref "R3") (pin "2") (pinfunction "2_2") (pintype "passive"))
      (node (ref "U$20") (pin "3") (pinfunction "+_3") (pintype "bidirectional"))
    )
    (net (code "54") (name "Net-(U$30A-+)") (class "Default")
      (node (ref "C2") (pin "1") (pinfunction "1_1") (pintype "passive"))
      (node (ref "R14") (pin "2") (pinfunction "2_2") (pintype "passive"))
      (node (ref "U$30") (pin "3") (pinfunction "+_3") (pintype "bidirectional"))
    )
    (net (code "55") (name "Net-(U$30A--)") (class "Default")
      (node (ref "C9") (pin "1") (pinfunction "1_1") (pintype "passive"))
      (node (ref "R12") (pin "1") (pinfunction "1_1") (pintype "passive"))
      (node (ref "R13") (pin "2") (pinfunction "2_2") (pintype "passive"))
      (node (ref "U$30") (pin "2") (pinfunction "-_2") (pintype "bidirectional"))
    )
    (net (code "56") (name "Net-(U$31A-+)") (class "Default")
      (node (ref "C14") (pin "2") (pinfunction "2_2") (pintype "passive"))
      (node (ref "R19") (pin "2") (pinfunction "2_2") (pintype "passive"))
      (node (ref "U$31") (pin "3") (pinfunction "+_3") (pintype "bidirectional"))
    )
    (net (code "57") (name "Net-(U$31A--)") (class "Default")
      (node (ref "C10") (pin "1") (pinfunction "1_1") (pintype "passive"))
      (node (ref "R15") (pin "1") (pinfunction "1_1") (pintype "passive"))
      (node (ref "R16") (pin "2") (pinfunction "2_2") (pintype "passive"))
      (node (ref "U$31") (pin "2") (pinfunction "-_2") (pintype "bidirectional"))
    )
    (net (code "58") (name "Net-(U$36A-+)") (class "Default")
      (node (ref "C15") (pin "2") (pinfunction "2_2") (pintype "passive"))
      (node (ref "R20") (pin "2") (pinfunction "2_2") (pintype "passive"))
      (node (ref "U$36") (pin "3") (pinfunction "+_3") (pintype "bidirectional"))
    )
    (net (code "59") (name "Net-(X2B-F)") (class "Default")
      (node (ref "JP3") (pin "2") (pinfunction "2_2") (pintype "passive"))
      (node (ref "X2") (pin "10") (pinfunction "F_10") (pintype "passive"))
    )
    (net (code "60") (name "Net-(X2C-F)") (class "Default")
      (node (ref "JP4") (pin "2") (pinfunction "2_2") (pintype "passive"))
      (node (ref "X2") (pin "11") (pinfunction "F_11") (pintype "passive"))
    )
    (net (code "61") (name "Net-(X2D-F)") (class "Default")
      (node (ref "JP5") (pin "2") (pinfunction "2_2") (pintype "passive"))
      (node (ref "X2") (pin "12") (pinfunction "F_12") (pintype "passive"))
    )
    (net (code "62") (name "Net-(X2E-F)") (class "Default")
      (node (ref "JP6") (pin "2") (pinfunction "2_2") (pintype "passive"))
      (node (ref "X2") (pin "13") (pinfunction "F_13") (pintype "passive"))
    )
    (net (code "63") (name "Net-(X2G-F)") (class "Default")
      (node (ref "R218") (pin "1") (pinfunction "1_1") (pintype "passive"))
      (node (ref "R6") (pin "1") (pinfunction "1_1") (pintype "passive"))
      (node (ref "X2") (pin "15") (pinfunction "F_15") (pintype "passive"))
    )
    (net (code "64") (name "Net-(X2M-F)") (class "Default")
      (node (ref "JP7") (pin "2") (pinfunction "2_2") (pintype "passive"))
      (node (ref "X2") (pin "20") (pinfunction "F_20") (pintype "passive"))
    )
    (net (code "65") (name "Net-(X2N-F)") (class "Default")
      (node (ref "JP8") (pin "2") (pinfunction "2_2") (pintype "passive"))
      (node (ref "X2") (pin "21") (pinfunction "F_21") (pintype "passive"))
    )
    (net (code "66") (name "Net-(X2O-F)") (class "Default")
      (node (ref "JP9") (pin "2") (pinfunction "2_2") (pintype "passive"))
      (node (ref "X2") (pin "22") (pinfunction "F_22") (pintype "passive"))
    )
    (net (code "67") (name "Net-(X2P-F)") (class "Default")
      (node (ref "JP10") (pin "2") (pinfunction "2_2") (pintype "passive"))
      (node (ref "X2") (pin "23") (pinfunction "F_23") (pintype "passive"))
    )
    (net (code "68") (name "Net-(X2Q-F)") (class "Default")
      (node (ref "JP11") (pin "2") (pinfunction "2_2") (pintype "passive"))
      (node (ref "X2") (pin "24") (pinfunction "F_24") (pintype "passive"))
    )
    (net (code "69") (name "Net-(X2R-F)") (class "Default")
      (node (ref "JP12") (pin "2") (pinfunction "2_2") (pintype "passive"))
      (node (ref "X2") (pin "25") (pinfunction "F_25") (pintype "passive"))
    )
    (net (code "70") (name "Net-(X2X-F)") (class "Default")
      (node (ref "JP1") (pin "2") (pinfunction "2_2") (pintype "passive"))
      (node (ref "X2") (pin "8") (pinfunction "F_8") (pintype "passive"))
    )
    (net (code "71") (name "Net-(X2Y-F)") (class "Default")
      (node (ref "JP2") (pin "2") (pinfunction "2_2") (pintype "passive"))
      (node (ref "X2") (pin "9") (pinfunction "F_9") (pintype "passive"))
    )
    (net (code "72") (name "unconnected-(IC1-BYP-Pad4)") (class "Default")
      (node (ref "IC1") (pin "4") (pinfunction "BYP_4") (pintype "passive"))
    )
    (net (code "73") (name "unconnected-(U$10A-C-Pad5)") (class "Default")
      (node (ref "U$10") (pin "5") (pinfunction "C_5") (pintype "bidirectional"))
    )
    (net (code "74") (name "unconnected-(U$12A-C-Pad5)") (class "Default")
      (node (ref "U$12") (pin "5") (pinfunction "C_5") (pintype "bidirectional"))
    )
    (net (code "75") (name "unconnected-(U$20A-C-Pad5)") (class "Default")
      (node (ref "U$20") (pin "5") (pinfunction "C_5") (pintype "bidirectional"))
    )
    (net (code "76") (name "unconnected-(U$30A-C-Pad5)") (class "Default")
      (node (ref "U$30") (pin "5") (pinfunction "C_5") (pintype "bidirectional"))
    )
    (net (code "77") (name "unconnected-(U$31A-C-Pad5)") (class "Default")
      (node (ref "U$31") (pin "5") (pinfunction "C_5") (pintype "bidirectional"))
    )
    (net (code "78") (name "unconnected-(U$36A-C-Pad5)") (class "Default")
      (node (ref "U$36") (pin "5") (pinfunction "C_5") (pintype "bidirectional"))
    )
  )
)
